# OpenPLCv0_2_0_Etherent.net
KiCad netlist of a schematic drawn in Altium Designer
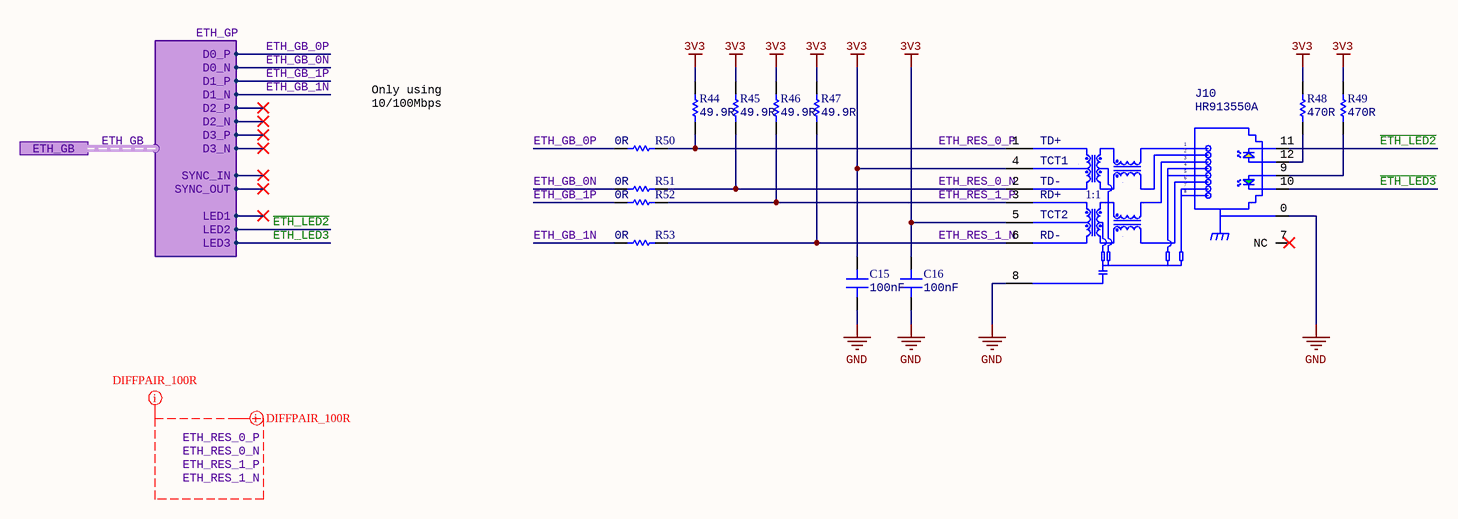
[diagram p0: OpenPLCv0.2.0_Etherent.SchDoc]

(export (version "E")
  (design (tool "Eeschema 10.0.6"))
  (components
    (comp (ref "C15")
      (value "CC0402KRX5R9BB104")
      (footprint "SMD_CAP_0402(1005)_N")
      (description "100nF ±10% 50V X5R 0402 Multilayer Ceramic Capacitors MLCC - SMD/SMT RoHS")
      (fields (field (name "TOLERANCE") "10%") (field (name "CAPACITANCE") "100nF"))
      (libsource (lib "BrauV2_Capacitor") (part "100nF 0402 50V 10%"))
    )
    (comp (ref "C16")
      (value "CC0402KRX5R9BB104")
      (footprint "SMD_CAP_0402(1005)_N")
      (description "100nF ±10% 50V X5R 0402 Multilayer Ceramic Capacitors MLCC - SMD/SMT RoHS")
      (fields (field (name "TOLERANCE") "10%") (field (name "CAPACITANCE") "100nF"))
      (libsource (lib "BrauV2_Capacitor") (part "100nF 0402 50V 10%"))
    )
    (comp (ref "J10")
      (value "HR913550A")
      (footprint "HR913550A")
      (description "RJ45 12 1 Green - Yellow Through Hole Ethernet Connectors/Modular Connectors (RJ45 RJ11) RoHS")
      (libsource (lib "BrauV2_Connector") (part "HR913550A"))
    )
    (comp (ref "R44")
      (value "RC0402FR-0749R9L")
      (footprint "SMD_RES_0402(1005)_N")
      (description "49.9Ω ±1% 1/16W ±100ppm/℃ 0402 Chip Resistor - Surface Mount RoHS")
      (fields (field (name "TOLERANCE") "1%") (field (name "RESISTANCE") "49.9R"))
      (libsource (lib "BrauV2_Resistor") (part "49R9 0402 1% 1/16W"))
    )
    (comp (ref "R45")
      (value "RC0402FR-0749R9L")
      (footprint "SMD_RES_0402(1005)_N")
      (description "49.9Ω ±1% 1/16W ±100ppm/℃ 0402 Chip Resistor - Surface Mount RoHS")
      (fields (field (name "TOLERANCE") "1%") (field (name "RESISTANCE") "49.9R"))
      (libsource (lib "BrauV2_Resistor") (part "49R9 0402 1% 1/16W"))
    )
    (comp (ref "R46")
      (value "RC0402FR-0749R9L")
      (footprint "SMD_RES_0402(1005)_N")
      (description "49.9Ω ±1% 1/16W ±100ppm/℃ 0402 Chip Resistor - Surface Mount RoHS")
      (fields (field (name "TOLERANCE") "1%") (field (name "RESISTANCE") "49.9R"))
      (libsource (lib "BrauV2_Resistor") (part "49R9 0402 1% 1/16W"))
    )
    (comp (ref "R47")
      (value "RC0402FR-0749R9L")
      (footprint "SMD_RES_0402(1005)_N")
      (description "49.9Ω ±1% 1/16W ±100ppm/℃ 0402 Chip Resistor - Surface Mount RoHS")
      (fields (field (name "TOLERANCE") "1%") (field (name "RESISTANCE") "49.9R"))
      (libsource (lib "BrauV2_Resistor") (part "49R9 0402 1% 1/16W"))
    )
    (comp (ref "R48")
      (value "RC0402FR-07470RL")
      (footprint "SMD_RES_0402(1005)_N")
      (description "470Ω ±1% 1/16W ±100ppm/℃ 0402 Chip Resistor - Surface Mount RoHS")
      (fields (field (name "TOLERANCE") "1%") (field (name "RESISTANCE") "470R"))
      (libsource (lib "BrauV2_Resistor") (part "470R 0402 1% 1W"))
    )
    (comp (ref "R49")
      (value "RC0402FR-07470RL")
      (footprint "SMD_RES_0402(1005)_N")
      (description "470Ω ±1% 1/16W ±100ppm/℃ 0402 Chip Resistor - Surface Mount RoHS")
      (fields (field (name "TOLERANCE") "1%") (field (name "RESISTANCE") "470R"))
      (libsource (lib "BrauV2_Resistor") (part "470R 0402 1% 1W"))
    )
    (comp (ref "R50")
      (value "RC0402FR-070RL")
      (footprint "SMD_RES_0402(1005)_N")
      (description "0Ω ±1% 1/16W 0402 Chip Resistor - Surface Mount RoHS")
      (fields (field (name "TOLERANCE") "1%") (field (name "RESISTANCE") "0R"))
      (libsource (lib "BrauV2_Resistor") (part "0R 0402 1% 1/16W"))
    )
    (comp (ref "R51")
      (value "RC0402FR-070RL")
      (footprint "SMD_RES_0402(1005)_N")
      (description "0Ω ±1% 1/16W 0402 Chip Resistor - Surface Mount RoHS")
      (fields (field (name "TOLERANCE") "1%") (field (name "RESISTANCE") "0R"))
      (libsource (lib "BrauV2_Resistor") (part "0R 0402 1% 1/16W"))
    )
    (comp (ref "R52")
      (value "RC0402FR-070RL")
      (footprint "SMD_RES_0402(1005)_N")
      (description "0Ω ±1% 1/16W 0402 Chip Resistor - Surface Mount RoHS")
      (fields (field (name "TOLERANCE") "1%") (field (name "RESISTANCE") "0R"))
      (libsource (lib "BrauV2_Resistor") (part "0R 0402 1% 1/16W"))
    )
    (comp (ref "R53")
      (value "RC0402FR-070RL")
      (footprint "SMD_RES_0402(1005)_N")
      (description "0Ω ±1% 1/16W 0402 Chip Resistor - Surface Mount RoHS")
      (fields (field (name "TOLERANCE") "1%") (field (name "RESISTANCE") "0R"))
      (libsource (lib "BrauV2_Resistor") (part "0R 0402 1% 1/16W"))
    )
  )
  (nets
    (net (code "2") (name "/ETH_GB_0N") (class "Default")
      (node (ref "R51") (pin "1") (pinfunction "1_1") (pintype "passive"))
    )
    (net (code "3") (name "/ETH_GB_0P") (class "Default")
      (node (ref "R50") (pin "1") (pinfunction "1_1") (pintype "passive"))
    )
    (net (code "4") (name "/ETH_GB_1N") (class "Default")
      (node (ref "R53") (pin "1") (pinfunction "1_1") (pintype "passive"))
    )
    (net (code "5") (name "/ETH_GB_1P") (class "Default")
      (node (ref "R52") (pin "1") (pinfunction "1_1") (pintype "passive"))
    )
    (net (code "7") (name "/ETH_RES_0_N") (class "Default")
      (node (ref "J10") (pin "2") (pinfunction "TD-_2") (pintype "passive"))
      (node (ref "R45") (pin "1") (pinfunction "1_1") (pintype "passive"))
      (node (ref "R51") (pin "2") (pinfunction "2_2") (pintype "passive"))
    )
    (net (code "8") (name "/ETH_RES_0_P") (class "Default")
      (node (ref "J10") (pin "1") (pinfunction "TD+_1") (pintype "passive"))
      (node (ref "R44") (pin "1") (pinfunction "1_1") (pintype "passive"))
      (node (ref "R50") (pin "2") (pinfunction "2_2") (pintype "passive"))
    )
    (net (code "9") (name "/ETH_RES_1_N") (class "Default")
      (node (ref "J10") (pin "6") (pinfunction "RD-_6") (pintype "passive"))
      (node (ref "R47") (pin "1") (pinfunction "1_1") (pintype "passive"))
      (node (ref "R53") (pin "2") (pinfunction "2_2") (pintype "passive"))
    )
    (net (code "10") (name "/ETH_RES_1_P") (class "Default")
      (node (ref "J10") (pin "3") (pinfunction "RD+_3") (pintype "passive"))
      (node (ref "R46") (pin "1") (pinfunction "1_1") (pintype "passive"))
      (node (ref "R52") (pin "2") (pinfunction "2_2") (pintype "passive"))
    )
    (net (code "11") (name "/~{ETH_LED2}") (class "Default")
      (node (ref "J10") (pin "11") (pinfunction "YLED-_11") (pintype "passive"))
    )
    (net (code "12") (name "/~{ETH_LED3}") (class "Default")
      (node (ref "J10") (pin "10") (pinfunction "GLED+_10") (pintype "passive"))
    )
    (net (code "13") (name "3V3") (class "Default")
      (node (ref "C15") (pin "2") (pinfunction "2_2") (pintype "passive"))
      (node (ref "C16") (pin "2") (pinfunction "2_2") (pintype "passive"))
      (node (ref "J10") (pin "4") (pinfunction "TCT1_4") (pintype "passive"))
      (node (ref "J10") (pin "5") (pinfunction "TCT2_5") (pintype "passive"))
      (node (ref "R44") (pin "2") (pinfunction "2_2") (pintype "passive"))
      (node (ref "R45") (pin "2") (pinfunction "2_2") (pintype "passive"))
      (node (ref "R46") (pin "2") (pinfunction "2_2") (pintype "passive"))
      (node (ref "R47") (pin "2") (pinfunction "2_2") (pintype "passive"))
      (node (ref "R48") (pin "2") (pinfunction "2_2") (pintype "passive"))
      (node (ref "R49") (pin "2") (pinfunction "2_2") (pintype "passive"))
    )
    (net (code "14") (name "GND") (class "Default")
      (node (ref "C15") (pin "1") (pinfunction "1_1") (pintype "passive"))
      (node (ref "C16") (pin "1") (pinfunction "1_1") (pintype "passive"))
      (node (ref "J10") (pin "0") (pinfunction "SHLD_0") (pintype "passive"))
      (node (ref "J10") (pin "8") (pinfunction "GND_8") (pintype "passive"))
    )
    (net (code "15") (name "Net-(J10-OLED+)") (class "Default")
      (node (ref "J10") (pin "9") (pinfunction "OLED+_9") (pintype "passive"))
      (node (ref "R49") (pin "1") (pinfunction "1_1") (pintype "passive"))
    )
    (net (code "16") (name "Net-(J10-YLED+)") (class "Default")
      (node (ref "J10") (pin "12") (pinfunction "YLED+_12") (pintype "passive"))
      (node (ref "R48") (pin "1") (pinfunction "1_1") (pintype "passive"))
    )
    (net (code "17") (name "unconnected-(J10-NC-Pad7)") (class "Default")
      (node (ref "J10") (pin "7") (pinfunction "NC_7") (pintype "passive+no_connect"))
    )
  )
)
